# CC2540.net
KiCad netlist of a schematic drawn in Altium Designer
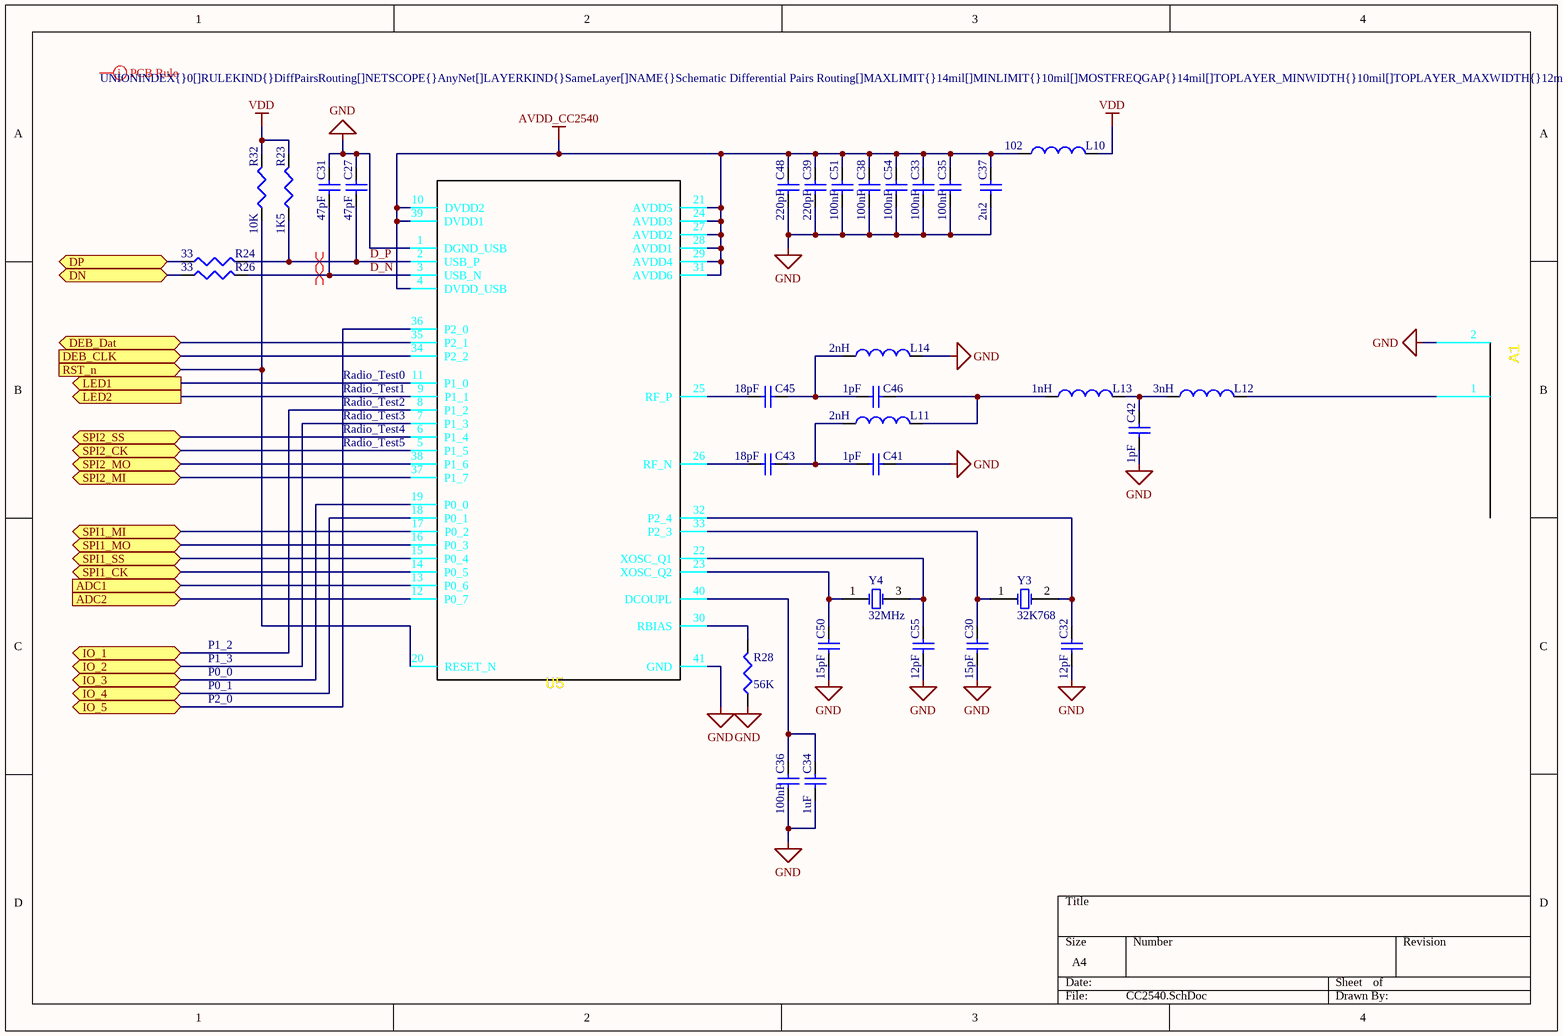
[diagram p0: CC2540.SchDoc]

(export (version "E")
  (design (tool "Eeschema 10.0.6"))
  (components
    (comp (ref "A1")
      (value "Antenna_IIFA_1")
      (footprint "antenna_IIFA_1")
      (description "Antenna single ended IIFA, 2450 MHz")
      (libsource (lib "mdap") (part "Antenna_IIFA_1"))
    )
    (comp (ref "C27")
      (value "47pF")
      (footprint "0402")
      (description "Capacitor")
      (fields
        (field (name "MANUFACTURER") "FARNELL")
        (field (name "Comment") "Cap")
        (field (name "PUBLISHER") "Altium Limited")
      )
      (libsource (lib "Miscellaneous Devices") (part "Cap"))
    )
    (comp (ref "C30")
      (value "15pF")
      (footprint "0402")
      (description "Capacitor")
      (fields
        (field (name "MANUFACTURER") "FARNELL")
        (field (name "Comment") "Cap")
        (field (name "PUBLISHER") "Altium Limited")
      )
      (libsource (lib "Miscellaneous Devices") (part "Cap"))
    )
    (comp (ref "C31")
      (value "47pF")
      (footprint "0402")
      (description "Capacitor")
      (fields
        (field (name "MANUFACTURER") "FARNELL")
        (field (name "Comment") "Cap")
        (field (name "PUBLISHER") "Altium Limited")
      )
      (libsource (lib "Miscellaneous Devices") (part "Cap"))
    )
    (comp (ref "C32")
      (value "12pF")
      (footprint "0402")
      (description "Capacitor")
      (fields
        (field (name "MANUFACTURER") "FARNELL")
        (field (name "Comment") "Cap")
        (field (name "PUBLISHER") "Altium Limited")
      )
      (libsource (lib "Miscellaneous Devices") (part "Cap"))
    )
    (comp (ref "C33")
      (value "100nF")
      (footprint "0402")
      (description "Capacitor")
      (fields
        (field (name "MANUFACTURER") "FARNELL")
        (field (name "Comment") "Cap")
        (field (name "PUBLISHER") "Altium Limited")
      )
      (libsource (lib "Miscellaneous Devices") (part "Cap"))
    )
    (comp (ref "C34")
      (value "1uF")
      (footprint "C0805")
      (description "Capacitor")
      (fields
        (field (name "MANUFACTURER") "FARNELL")
        (field (name "Comment") "Cap")
        (field (name "PUBLISHER") "Altium Limited")
      )
      (libsource (lib "Miscellaneous Devices") (part "Cap"))
    )
    (comp (ref "C35")
      (value "100nF")
      (footprint "0402")
      (description "Capacitor")
      (fields
        (field (name "MANUFACTURER") "FARNELL")
        (field (name "Comment") "Cap")
        (field (name "PUBLISHER") "Altium Limited")
      )
      (libsource (lib "Miscellaneous Devices") (part "Cap"))
    )
    (comp (ref "C36")
      (value "100nF")
      (footprint "0402")
      (description "Capacitor")
      (fields
        (field (name "MANUFACTURER") "FARNELL")
        (field (name "Comment") "Cap")
        (field (name "PUBLISHER") "Altium Limited")
      )
      (libsource (lib "Miscellaneous Devices") (part "Cap"))
    )
    (comp (ref "C37")
      (value "2u2")
      (footprint "C0805")
      (description "Capacitor")
      (fields
        (field (name "MANUFACTURER") "FARNELL")
        (field (name "Comment") "Cap")
        (field (name "PUBLISHER") "Altium Limited")
      )
      (libsource (lib "Miscellaneous Devices") (part "Cap"))
    )
    (comp (ref "C38")
      (value "100nF")
      (footprint "0402")
      (description "Capacitor")
      (fields
        (field (name "MANUFACTURER") "FARNELL")
        (field (name "Comment") "Cap")
        (field (name "PUBLISHER") "Altium Limited")
      )
      (libsource (lib "Miscellaneous Devices") (part "Cap"))
    )
    (comp (ref "C39")
      (value "220pF")
      (footprint "0402")
      (description "Capacitor")
      (fields
        (field (name "MANUFACTURER") "FARNELL")
        (field (name "Comment") "Cap")
        (field (name "PUBLISHER") "Altium Limited")
      )
      (libsource (lib "Miscellaneous Devices") (part "Cap"))
    )
    (comp (ref "C41")
      (value "1pF")
      (footprint "0402")
      (description "Capacitor")
      (fields
        (field (name "MANUFACTURER") "FARNELL")
        (field (name "Comment") "Cap")
        (field (name "PUBLISHER") "Altium Limited")
      )
      (libsource (lib "Miscellaneous Devices") (part "Cap"))
    )
    (comp (ref "C42")
      (value "1pF")
      (footprint "0402")
      (description "Capacitor")
      (fields
        (field (name "MANUFACTURER") "FARNELL")
        (field (name "Comment") "Cap")
        (field (name "PUBLISHER") "Altium Limited")
      )
      (libsource (lib "Miscellaneous Devices") (part "Cap"))
    )
    (comp (ref "C43")
      (value "18pF")
      (footprint "0402")
      (description "Capacitor")
      (fields
        (field (name "MANUFACTURER") "FARNELL")
        (field (name "Comment") "Cap")
        (field (name "PUBLISHER") "Altium Limited")
      )
      (libsource (lib "Miscellaneous Devices") (part "Cap"))
    )
    (comp (ref "C45")
      (value "18pF")
      (footprint "0402")
      (description "Capacitor")
      (fields
        (field (name "MANUFACTURER") "FARNELL")
        (field (name "Comment") "Cap")
        (field (name "PUBLISHER") "Altium Limited")
      )
      (libsource (lib "Miscellaneous Devices") (part "Cap"))
    )
    (comp (ref "C46")
      (value "1pF")
      (footprint "0402")
      (description "Capacitor")
      (fields
        (field (name "MANUFACTURER") "FARNELL")
        (field (name "Comment") "Cap")
        (field (name "PUBLISHER") "Altium Limited")
      )
      (libsource (lib "Miscellaneous Devices") (part "Cap"))
    )
    (comp (ref "C48")
      (value "220pF")
      (footprint "0402")
      (description "Capacitor")
      (fields
        (field (name "MANUFACTURER") "FARNELL")
        (field (name "Comment") "Cap")
        (field (name "PUBLISHER") "Altium Limited")
      )
      (libsource (lib "Miscellaneous Devices") (part "Cap"))
    )
    (comp (ref "C50")
      (value "15pF")
      (footprint "0402")
      (description "Capacitor")
      (fields
        (field (name "MANUFACTURER") "FARNELL")
        (field (name "Comment") "Cap")
        (field (name "PUBLISHER") "Altium Limited")
      )
      (libsource (lib "Miscellaneous Devices") (part "Cap"))
    )
    (comp (ref "C51")
      (value "100nF")
      (footprint "0402")
      (description "Capacitor")
      (fields
        (field (name "MANUFACTURER") "FARNELL")
        (field (name "Comment") "Cap")
        (field (name "PUBLISHER") "Altium Limited")
      )
      (libsource (lib "Miscellaneous Devices") (part "Cap"))
    )
    (comp (ref "C54")
      (value "100nF")
      (footprint "0402")
      (description "Capacitor")
      (fields
        (field (name "MANUFACTURER") "FARNELL")
        (field (name "Comment") "Cap")
        (field (name "PUBLISHER") "Altium Limited")
      )
      (libsource (lib "Miscellaneous Devices") (part "Cap"))
    )
    (comp (ref "C55")
      (value "12pF")
      (footprint "0402")
      (description "Capacitor")
      (fields
        (field (name "MANUFACTURER") "FARNELL")
        (field (name "Comment") "Cap")
        (field (name "PUBLISHER") "Altium Limited")
      )
      (libsource (lib "Miscellaneous Devices") (part "Cap"))
    )
    (comp (ref "L10")
      (value "102")
      (footprint "0402-A")
      (description "Inductor")
      (fields (field (name "MANUFACTURER") "FARNELL") (field (name "PUBLISHER") "Altium Limited"))
      (libsource (lib "Miscellaneous Devices") (part "Inductor"))
    )
    (comp (ref "L11")
      (value "2nH")
      (footprint "0402-A")
      (description "Inductor")
      (fields (field (name "MANUFACTURER") "FARNELL") (field (name "PUBLISHER") "Altium Limited"))
      (libsource (lib "Miscellaneous Devices") (part "Inductor"))
    )
    (comp (ref "L12")
      (value "3nH")
      (footprint "0402-A")
      (description "Inductor")
      (fields (field (name "MANUFACTURER") "FARNELL") (field (name "PUBLISHER") "Altium Limited"))
      (libsource (lib "Miscellaneous Devices") (part "Inductor"))
    )
    (comp (ref "L13")
      (value "1nH")
      (footprint "0402-A")
      (description "Inductor")
      (fields (field (name "MANUFACTURER") "FARNELL") (field (name "PUBLISHER") "Altium Limited"))
      (libsource (lib "Miscellaneous Devices") (part "Inductor"))
    )
    (comp (ref "L14")
      (value "2nH")
      (footprint "0402-A")
      (description "Inductor")
      (fields (field (name "MANUFACTURER") "FARNELL") (field (name "PUBLISHER") "Altium Limited"))
      (libsource (lib "Miscellaneous Devices") (part "Inductor"))
    )
    (comp (ref "R23")
      (value "1K5")
      (footprint "J1-0603")
      (description "Resistor")
      (fields
        (field (name "MANUFACTURER") "FARNELL")
        (field (name "Comment") "Res3")
        (field (name "PUBLISHER") "Altium Limited")
      )
      (libsource (lib "Miscellaneous Devices") (part "Res3"))
    )
    (comp (ref "R24")
      (value "33")
      (footprint "J1-0603")
      (description "Resistor")
      (fields
        (field (name "MANUFACTURER") "FARNELL")
        (field (name "Comment") "Res3")
        (field (name "PUBLISHER") "Altium Limited")
      )
      (libsource (lib "Miscellaneous Devices") (part "Res3"))
    )
    (comp (ref "R26")
      (value "33")
      (footprint "J1-0603")
      (description "Resistor")
      (fields
        (field (name "MANUFACTURER") "FARNELL")
        (field (name "Comment") "Res3")
        (field (name "PUBLISHER") "Altium Limited")
      )
      (libsource (lib "Miscellaneous Devices") (part "Res3"))
    )
    (comp (ref "R28")
      (value "56K")
      (footprint "J1-0603")
      (description "Resistor")
      (fields
        (field (name "MANUFACTURER") "FARNELL")
        (field (name "Comment") "Res3")
        (field (name "PUBLISHER") "Altium Limited")
      )
      (libsource (lib "Miscellaneous Devices") (part "Res3"))
    )
    (comp (ref "R32")
      (value "10K")
      (footprint "J1-0603")
      (description "Resistor")
      (fields
        (field (name "MANUFACTURER") "FARNELL")
        (field (name "Comment") "Res3")
        (field (name "PUBLISHER") "Altium Limited")
      )
      (libsource (lib "Miscellaneous Devices") (part "Res3"))
    )
    (comp (ref "U5")
      (value "CC2540")
      (footprint "QFN40_RHA (DATASHEET)")
      (description "Single chip BLE")
      (fields (field (name "MANUFACTURER") "FARNELL"))
      (libsource (lib "mdap") (part "CC2540"))
    )
    (comp (ref "Y3")
      (value "32K768")
      (footprint "xtal_3215")
      (description "Crystal Oscillator")
      (fields (field (name "MANUFACTURER") "Smart Prototyping"))
      (libsource (lib "Miscellaneous Devices") (part "XTAL"))
    )
    (comp (ref "Y4")
      (value "32MHz")
      (footprint "xtal_3225")
      (description "Crystal Oscillator")
      (fields (field (name "MANUFACTURER") "Smart Prototyping"))
      (libsource (lib "MDAP") (part "XTAL_4"))
    )
  )
  (nets
    (net (code "1") (name "/ADC1") (class "Default")
      (node (ref "U5") (pin "13") (pinfunction "P0_6_13") (pintype "passive"))
    )
    (net (code "2") (name "/ADC2") (class "Default")
      (node (ref "U5") (pin "12") (pinfunction "P0_7_12") (pintype "passive"))
    )
    (net (code "3") (name "/DEB_CLK") (class "Default")
      (node (ref "U5") (pin "34") (pinfunction "P2_2_34") (pintype "passive"))
    )
    (net (code "4") (name "/DEB_Dat") (class "Default")
      (node (ref "U5") (pin "35") (pinfunction "P2_1_35") (pintype "passive"))
    )
    (net (code "5") (name "/DN") (class "Default")
      (node (ref "R26") (pin "1") (pinfunction "1_1") (pintype "passive"))
    )
    (net (code "6") (name "/DP") (class "Default")
      (node (ref "R24") (pin "1") (pinfunction "1_1") (pintype "passive"))
    )
    (net (code "7") (name "/D_N") (class "Default")
      (node (ref "C31") (pin "1") (pinfunction "1_1") (pintype "passive"))
      (node (ref "R26") (pin "2") (pinfunction "2_2") (pintype "passive"))
      (node (ref "U5") (pin "3") (pinfunction "USB_N_3") (pintype "passive"))
    )
    (net (code "8") (name "/D_P") (class "Default")
      (node (ref "C27") (pin "1") (pinfunction "1_1") (pintype "passive"))
      (node (ref "R23") (pin "1") (pinfunction "1_1") (pintype "passive"))
      (node (ref "R24") (pin "2") (pinfunction "2_2") (pintype "passive"))
      (node (ref "U5") (pin "2") (pinfunction "USB_P_2") (pintype "passive"))
    )
    (net (code "9") (name "/IO_1") (class "Default")
      (node (ref "U5") (pin "8") (pinfunction "P1_2_8") (pintype "passive"))
    )
    (net (code "10") (name "/IO_2") (class "Default")
      (node (ref "U5") (pin "7") (pinfunction "P1_3_7") (pintype "passive"))
    )
    (net (code "11") (name "/IO_3") (class "Default")
      (node (ref "U5") (pin "19") (pinfunction "P0_0_19") (pintype "passive"))
    )
    (net (code "12") (name "/IO_4") (class "Default")
      (node (ref "U5") (pin "18") (pinfunction "P0_1_18") (pintype "passive"))
    )
    (net (code "13") (name "/IO_5") (class "Default")
      (node (ref "U5") (pin "36") (pinfunction "P2_0_36") (pintype "passive"))
    )
    (net (code "14") (name "/LED1") (class "Default")
      (node (ref "U5") (pin "11") (pinfunction "P1_0_11") (pintype "passive"))
    )
    (net (code "15") (name "/LED2") (class "Default")
      (node (ref "U5") (pin "9") (pinfunction "P1_1_9") (pintype "passive"))
    )
    (net (code "16") (name "/RST_n") (class "Default")
      (node (ref "R32") (pin "1") (pinfunction "1_1") (pintype "passive"))
      (node (ref "U5") (pin "20") (pinfunction "RESET_N_20") (pintype "passive"))
    )
    (net (code "17") (name "/SPI1_CK") (class "Default")
      (node (ref "U5") (pin "14") (pinfunction "P0_5_14") (pintype "passive"))
    )
    (net (code "18") (name "/SPI1_MI") (class "Default")
      (node (ref "U5") (pin "17") (pinfunction "P0_2_17") (pintype "passive"))
    )
    (net (code "19") (name "/SPI1_MO") (class "Default")
      (node (ref "U5") (pin "16") (pinfunction "P0_3_16") (pintype "passive"))
    )
    (net (code "20") (name "/SPI1_SS") (class "Default")
      (node (ref "U5") (pin "15") (pinfunction "P0_4_15") (pintype "passive"))
    )
    (net (code "21") (name "/SPI2_CK") (class "Default")
      (node (ref "U5") (pin "5") (pinfunction "P1_5_5") (pintype "passive"))
    )
    (net (code "22") (name "/SPI2_MI") (class "Default")
      (node (ref "U5") (pin "37") (pinfunction "P1_7_37") (pintype "passive"))
    )
    (net (code "23") (name "/SPI2_MO") (class "Default")
      (node (ref "U5") (pin "38") (pinfunction "P1_6_38") (pintype "passive"))
    )
    (net (code "24") (name "/SPI2_SS") (class "Default")
      (node (ref "U5") (pin "6") (pinfunction "P1_4_6") (pintype "passive"))
    )
    (net (code "25") (name "AVDD_CC2540") (class "Default")
      (node (ref "C33") (pin "2") (pinfunction "2_2") (pintype "passive"))
      (node (ref "C35") (pin "2") (pinfunction "2_2") (pintype "passive"))
      (node (ref "C37") (pin "2") (pinfunction "2_2") (pintype "passive"))
      (node (ref "C38") (pin "2") (pinfunction "2_2") (pintype "passive"))
      (node (ref "C39") (pin "2") (pinfunction "2_2") (pintype "passive"))
      (node (ref "C48") (pin "2") (pinfunction "2_2") (pintype "passive"))
      (node (ref "C51") (pin "2") (pinfunction "2_2") (pintype "passive"))
      (node (ref "C54") (pin "2") (pinfunction "2_2") (pintype "passive"))
      (node (ref "L10") (pin "1") (pinfunction "1_1") (pintype "passive"))
      (node (ref "U5") (pin "10") (pinfunction "DVDD2_10") (pintype "passive"))
      (node (ref "U5") (pin "21") (pinfunction "AVDD5_21") (pintype "passive"))
      (node (ref "U5") (pin "24") (pinfunction "AVDD3_24") (pintype "passive"))
      (node (ref "U5") (pin "27") (pinfunction "AVDD2_27") (pintype "passive"))
      (node (ref "U5") (pin "28") (pinfunction "AVDD1_28") (pintype "passive"))
      (node (ref "U5") (pin "29") (pinfunction "AVDD4_29") (pintype "passive"))
      (node (ref "U5") (pin "31") (pinfunction "AVDD6_31") (pintype "passive"))
      (node (ref "U5") (pin "39") (pinfunction "DVDD1_39") (pintype "passive"))
      (node (ref "U5") (pin "4") (pinfunction "DVDD_USB_4") (pintype "passive"))
    )
    (net (code "26") (name "GND") (class "Default")
      (node (ref "A1") (pin "2") (pintype "passive"))
      (node (ref "C27") (pin "2") (pinfunction "2_2") (pintype "passive"))
      (node (ref "C30") (pin "1") (pinfunction "1_1") (pintype "passive"))
      (node (ref "C31") (pin "2") (pinfunction "2_2") (pintype "passive"))
      (node (ref "C32") (pin "1") (pinfunction "1_1") (pintype "passive"))
      (node (ref "C33") (pin "1") (pinfunction "1_1") (pintype "passive"))
      (node (ref "C34") (pin "1") (pinfunction "1_1") (pintype "passive"))
      (node (ref "C35") (pin "1") (pinfunction "1_1") (pintype "passive"))
      (node (ref "C36") (pin "1") (pinfunction "1_1") (pintype "passive"))
      (node (ref "C37") (pin "1") (pinfunction "1_1") (pintype "passive"))
      (node (ref "C38") (pin "1") (pinfunction "1_1") (pintype "passive"))
      (node (ref "C39") (pin "1") (pinfunction "1_1") (pintype "passive"))
      (node (ref "C41") (pin "1") (pinfunction "1_1") (pintype "passive"))
      (node (ref "C42") (pin "1") (pinfunction "1_1") (pintype "passive"))
      (node (ref "C48") (pin "1") (pinfunction "1_1") (pintype "passive"))
      (node (ref "C50") (pin "1") (pinfunction "1_1") (pintype "passive"))
      (node (ref "C51") (pin "1") (pinfunction "1_1") (pintype "passive"))
      (node (ref "C54") (pin "1") (pinfunction "1_1") (pintype "passive"))
      (node (ref "C55") (pin "1") (pinfunction "1_1") (pintype "passive"))
      (node (ref "L14") (pin "2") (pinfunction "2_2") (pintype "passive"))
      (node (ref "R28") (pin "1") (pinfunction "1_1") (pintype "passive"))
      (node (ref "U5") (pin "1") (pinfunction "DGND_USB_1") (pintype "passive"))
      (node (ref "U5") (pin "41") (pinfunction "GND_41") (pintype "passive"))
    )
    (net (code "27") (name "Net-(A1-Pad1)") (class "Default")
      (node (ref "A1") (pin "1") (pintype "passive"))
      (node (ref "L12") (pin "2") (pinfunction "2_2") (pintype "passive"))
    )
    (net (code "28") (name "Net-(C41-Pad2)") (class "Default")
      (node (ref "C41") (pin "2") (pinfunction "2_2") (pintype "passive"))
      (node (ref "C43") (pin "1") (pinfunction "1_1") (pintype "passive"))
      (node (ref "L11") (pin "1") (pinfunction "1_1") (pintype "passive"))
    )
    (net (code "29") (name "Net-(C42-Pad2)") (class "Default")
      (node (ref "C42") (pin "2") (pinfunction "2_2") (pintype "passive"))
      (node (ref "L12") (pin "1") (pinfunction "1_1") (pintype "passive"))
      (node (ref "L13") (pin "2") (pinfunction "2_2") (pintype "passive"))
    )
    (net (code "30") (name "Net-(C45-Pad1)") (class "Default")
      (node (ref "C45") (pin "1") (pinfunction "1_1") (pintype "passive"))
      (node (ref "C46") (pin "2") (pinfunction "2_2") (pintype "passive"))
      (node (ref "L14") (pin "1") (pinfunction "1_1") (pintype "passive"))
    )
    (net (code "31") (name "Net-(C46-Pad1)") (class "Default")
      (node (ref "C46") (pin "1") (pinfunction "1_1") (pintype "passive"))
      (node (ref "L11") (pin "2") (pinfunction "2_2") (pintype "passive"))
      (node (ref "L13") (pin "1") (pinfunction "1_1") (pintype "passive"))
    )
    (net (code "32") (name "Net-(U5-DCOUPL)") (class "Default")
      (node (ref "C34") (pin "2") (pinfunction "2_2") (pintype "passive"))
      (node (ref "C36") (pin "2") (pinfunction "2_2") (pintype "passive"))
      (node (ref "U5") (pin "40") (pinfunction "DCOUPL_40") (pintype "passive"))
    )
    (net (code "33") (name "Net-(U5-P2_3)") (class "Default")
      (node (ref "C30") (pin "2") (pinfunction "2_2") (pintype "passive"))
      (node (ref "U5") (pin "33") (pinfunction "P2_3_33") (pintype "passive"))
      (node (ref "Y3") (pin "1") (pinfunction "OSC1_1") (pintype "passive"))
    )
    (net (code "34") (name "Net-(U5-P2_4)") (class "Default")
      (node (ref "C32") (pin "2") (pinfunction "2_2") (pintype "passive"))
      (node (ref "U5") (pin "32") (pinfunction "P2_4_32") (pintype "passive"))
      (node (ref "Y3") (pin "2") (pinfunction "OSC2_2") (pintype "passive"))
    )
    (net (code "35") (name "Net-(U5-RBIAS)") (class "Default")
      (node (ref "R28") (pin "2") (pinfunction "2_2") (pintype "passive"))
      (node (ref "U5") (pin "30") (pinfunction "RBIAS_30") (pintype "passive"))
    )
    (net (code "36") (name "Net-(U5-RF_N)") (class "Default")
      (node (ref "C43") (pin "2") (pinfunction "2_2") (pintype "passive"))
      (node (ref "U5") (pin "26") (pinfunction "RF_N_26") (pintype "passive"))
    )
    (net (code "37") (name "Net-(U5-RF_P)") (class "Default")
      (node (ref "C45") (pin "2") (pinfunction "2_2") (pintype "passive"))
      (node (ref "U5") (pin "25") (pinfunction "RF_P_25") (pintype "passive"))
    )
    (net (code "38") (name "Net-(U5-XOSC_Q1)") (class "Default")
      (node (ref "C55") (pin "2") (pinfunction "2_2") (pintype "passive"))
      (node (ref "U5") (pin "22") (pinfunction "XOSC_Q1_22") (pintype "passive"))
      (node (ref "Y4") (pin "3") (pinfunction "OSC2_3") (pintype "passive"))
    )
    (net (code "39") (name "Net-(U5-XOSC_Q2)") (class "Default")
      (node (ref "C50") (pin "2") (pinfunction "2_2") (pintype "passive"))
      (node (ref "U5") (pin "23") (pinfunction "XOSC_Q2_23") (pintype "passive"))
      (node (ref "Y4") (pin "1") (pinfunction "OSC1_1") (pintype "passive"))
    )
    (net (code "40") (name "VDD") (class "Default")
      (node (ref "L10") (pin "2") (pinfunction "2_2") (pintype "passive"))
      (node (ref "R23") (pin "2") (pinfunction "2_2") (pintype "passive"))
      (node (ref "R32") (pin "2") (pinfunction "2_2") (pintype "passive"))
    )
  )
)
